# Prototype_Rx.net
KiCad netlist of a schematic drawn in EAGLE
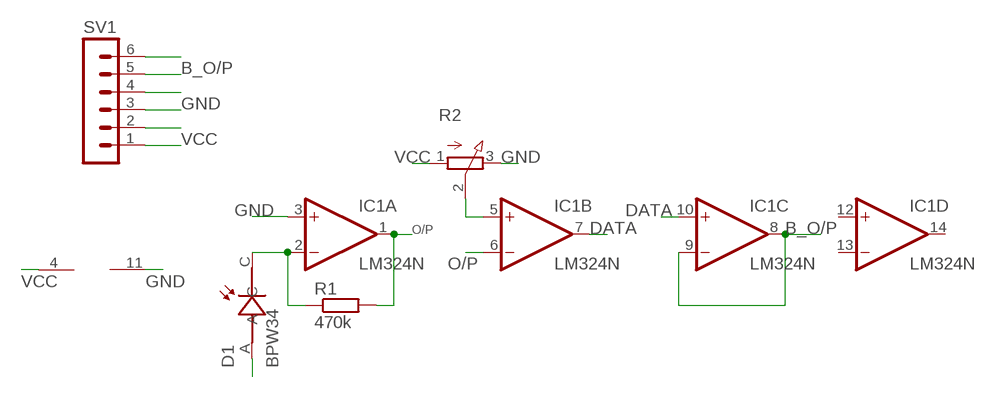
[diagram p0: schematic, sheet 1]

(export (version "E")
  (design (tool "Eeschema 10.0.6"))
  (components
    (comp (ref "D1")
      (value "BPW34")
      (footprint "eagle-import:PHODET_BPW34")
      (fields (field (name "MF") "Vishay Semiconductor"))
      (libsource (lib "eagle-import") (part "BPW34"))
    )
    (comp (ref "IC1")
      (value "LM324N")
      (footprint "eagle-import:DIL14")
      (libsource (lib "eagle-import") (part "LM324N"))
    )
    (comp (ref "R1")
      (value "470k")
      (footprint "eagle-import:0207_10")
      (libsource (lib "eagle-import") (part "R-EU_0207/10"))
    )
    (comp (ref "R2")
      (value "3RP/1610N")
      (footprint "eagle-import:3RP_1610N")
      (libsource (lib "eagle-import") (part "3RP/1610N"))
    )
    (comp (ref "SV1")
      (value "MA06-1")
      (footprint "eagle-import:MA06-1")
      (libsource (lib "eagle-import") (part "MA06-1"))
    )
  )
  (nets
    (net (code "1") (name "/B_O{slash}P") (class "Default")
      (node (ref "IC1") (pin "8") (pinfunction "OUT_8") (pintype "output"))
      (node (ref "IC1") (pin "9") (pinfunction "-IN_9") (pintype "input"))
      (node (ref "SV1") (pin "5") (pinfunction "5_5") (pintype "passive"))
      (node (ref "SV1") (pin "6") (pinfunction "6_6") (pintype "passive"))
    )
    (net (code "2") (name "/DATA") (class "Default")
      (node (ref "IC1") (pin "10") (pinfunction "+IN_10") (pintype "input"))
      (node (ref "IC1") (pin "7") (pinfunction "OUT_7") (pintype "output"))
    )
    (net (code "3") (name "/GND") (class "Default")
      (node (ref "D1") (pin "A") (pinfunction "A_A") (pintype "passive"))
      (node (ref "IC1") (pin "11") (pinfunction "V-_11") (pintype "power_in"))
      (node (ref "IC1") (pin "3") (pinfunction "+IN_3") (pintype "input"))
      (node (ref "R2") (pin "3") (pinfunction "E_3") (pintype "passive"))
      (node (ref "SV1") (pin "3") (pinfunction "3_3") (pintype "passive"))
      (node (ref "SV1") (pin "4") (pinfunction "4_4") (pintype "passive"))
    )
    (net (code "4") (name "/O{slash}P") (class "Default")
      (node (ref "IC1") (pin "1") (pinfunction "OUT_1") (pintype "output"))
      (node (ref "IC1") (pin "6") (pinfunction "-IN_6") (pintype "input"))
      (node (ref "R1") (pin "2") (pinfunction "2_2") (pintype "passive"))
    )
    (net (code "5") (name "/VCC") (class "Default")
      (node (ref "IC1") (pin "4") (pinfunction "V+_4") (pintype "power_in"))
      (node (ref "R2") (pin "1") (pinfunction "A_1") (pintype "passive"))
      (node (ref "SV1") (pin "1") (pinfunction "1_1") (pintype "passive"))
      (node (ref "SV1") (pin "2") (pinfunction "2_2") (pintype "passive"))
    )
    (net (code "6") (name "Net-(IC1A--IN)") (class "Default")
      (node (ref "D1") (pin "C") (pinfunction "C_C") (pintype "passive"))
      (node (ref "IC1") (pin "2") (pinfunction "-IN_2") (pintype "input"))
      (node (ref "R1") (pin "1") (pinfunction "1_1") (pintype "passive"))
    )
    (net (code "7") (name "Net-(IC1B-+IN)") (class "Default")
      (node (ref "IC1") (pin "5") (pinfunction "+IN_5") (pintype "input"))
      (node (ref "R2") (pin "2") (pinfunction "S_2") (pintype "passive"))
    )
    (net (code "8") (name "unconnected-(IC1D-+IN-Pad12)") (class "Default")
      (node (ref "IC1") (pin "12") (pinfunction "+IN_12") (pintype "input"))
    )
    (net (code "9") (name "unconnected-(IC1D--IN-Pad13)") (class "Default")
      (node (ref "IC1") (pin "13") (pinfunction "-IN_13") (pintype "input"))
    )
    (net (code "10") (name "unconnected-(IC1D-OUT-Pad14)") (class "Default")
      (node (ref "IC1") (pin "14") (pinfunction "OUT_14") (pintype "output"))
    )
  )
)
